# SCH_protopanda_v10.net
KiCad netlist of a schematic drawn in EasyEDA
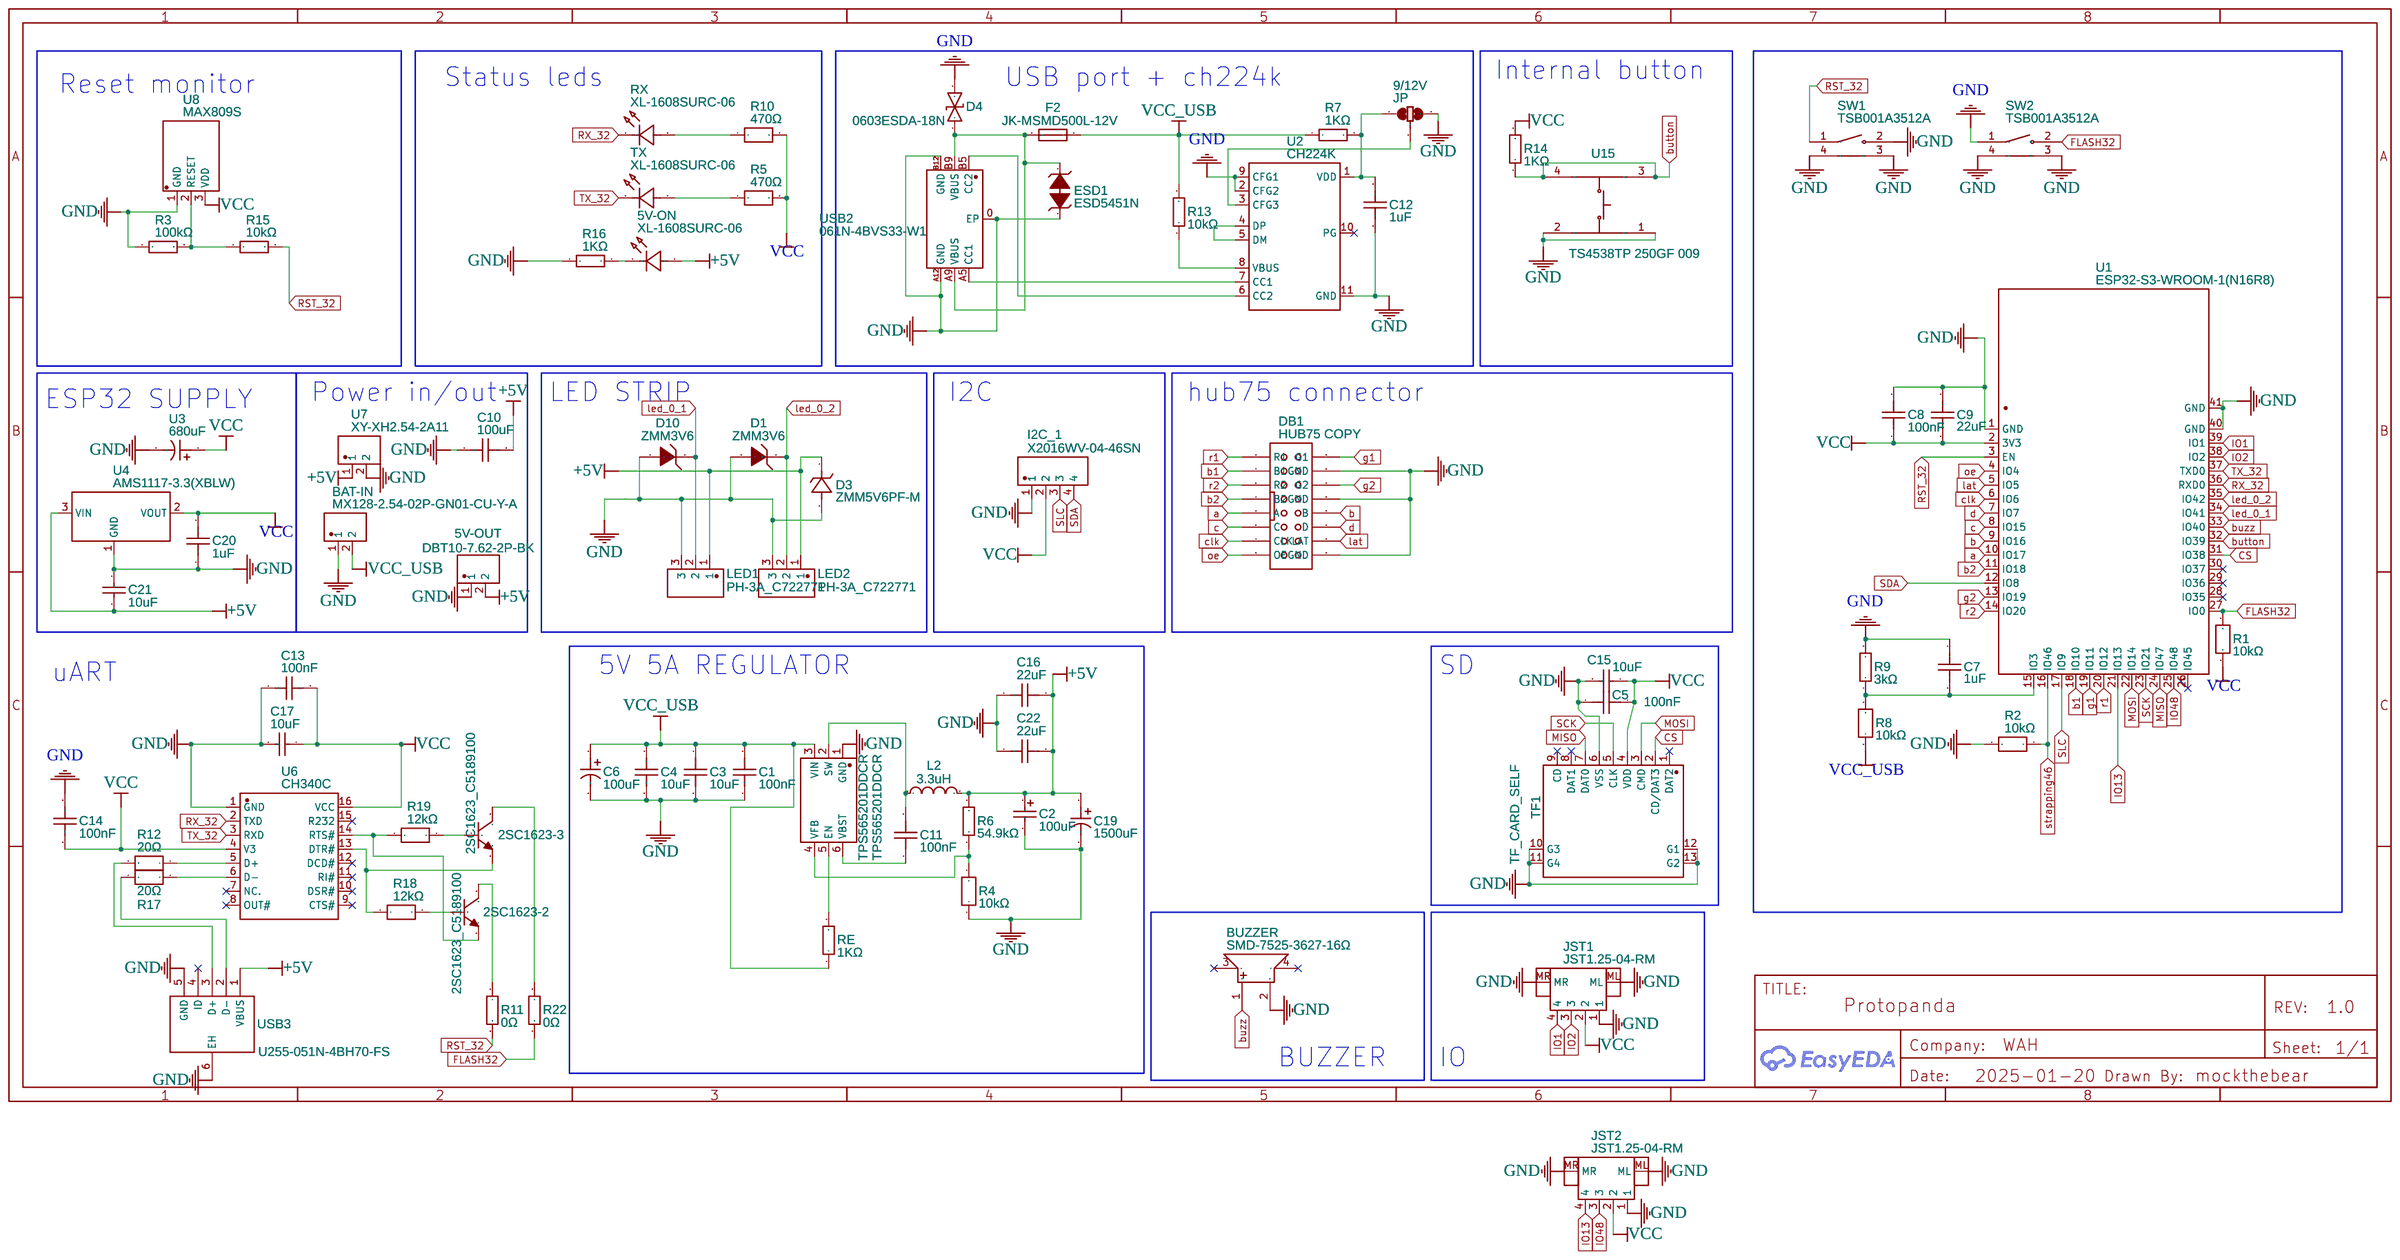
[diagram p0: schematic sheet]

(export (version "E")
  (design (tool "Eeschema 10.0.6"))
  (components
    (comp (ref "2SC1623-2")
      (value "2SC1623_C5189100")
      (fields (field (name "Manufacturer Part") "2SC1623") (field (name "Manufacturer") "HXY MOSFET(华轩阳电子)"))
      (libsource (lib "") (part "2SC1623_C5189100"))
    )
    (comp (ref "2SC1623-3")
      (value "2SC1623_C5189100")
      (fields (field (name "Manufacturer Part") "2SC1623") (field (name "Manufacturer") "HXY MOSFET(华轩阳电子)"))
      (libsource (lib "") (part "2SC1623_C5189100"))
    )
    (comp (ref "5V-ON")
      (value "XL-1608SURC-06")
      (fields (field (name "Manufacturer") "XINGLIGHT(成兴光)"))
      (libsource (lib "") (part "XL-1608SURC-06_1"))
    )
    (comp (ref "5V-OUT")
      (value "DBT10-7.62-2P-BK")
      (fields
        (field (name "Manufacturer Part") "DBT10-7.62-2P-BK-P")
        (field (name "Manufacturer") "DORABO(地博电气)")
      )
      (libsource (lib "") (part "DBT10-7.62-2P-BK"))
    )
    (comp (ref "9/12V") (value "JP") (libsource (lib "") (part "JUMPER-PAD-3-NOFULL_BOX_SILK")))
    (comp (ref "BAT-IN")
      (value "MX128-2.54-02P-GN01-CU-Y-A")
      (fields
        (field (name "Manufacturer Part") "MX128-2.54-02P-GN01-Cu-Y-A")
        (field (name "Manufacturer") "MAX(迈旭)")
      )
      (libsource (lib "") (part "MX128-2.54-02P-GN01-CU-Y-A"))
    )
    (comp (ref "BUZZER")
      (value "SMD-7525-3627-16Ω")
      (fields (field (name "Manufacturer") "S&S(海旭)"))
      (libsource (lib "") (part "SMD-7525-3627-16Ω"))
    )
    (comp (ref "C1")
      (value "100nF")
      (fields
        (field (name "Manufacturer Part") "CC0603KRX7R6BB104")
        (field (name "Manufacturer") "YAGEO(国巨)")
      )
      (libsource (lib "") (part "CC0603KRX7R6BB104_1"))
    )
    (comp (ref "C2")
      (value "100uF")
      (fields
        (field (name "Manufacturer Part") "T490A107M006ATE800")
        (field (name "Manufacturer") "KEMET(基美)")
      )
      (libsource (lib "") (part "T490A107M006ATE800"))
    )
    (comp (ref "C3")
      (value "10uF")
      (fields (field (name "Manufacturer Part") "CC0603CRNPO9BN5R1") (field (name "Manufacturer") "YAGEO"))
      (libsource (lib "") (part "CC0603CRNPO9BN5R1"))
    )
    (comp (ref "C4")
      (value "10uF")
      (fields (field (name "Manufacturer Part") "CC0603CRNPO9BN5R1") (field (name "Manufacturer") "YAGEO"))
      (libsource (lib "") (part "CC0603CRNPO9BN5R1"))
    )
    (comp (ref "C5")
      (value "100nF")
      (fields
        (field (name "Manufacturer Part") "CC0603KRX7R6BB104")
        (field (name "Manufacturer") "YAGEO(国巨)")
      )
      (libsource (lib "") (part "CC0603KRX7R6BB104"))
    )
    (comp (ref "C6")
      (value "100uF")
      (fields
        (field (name "Manufacturer Part") "RVT100UF25V67RV0011")
        (field (name "Manufacturer") "KNSCHA(科尼盛)")
      )
      (libsource (lib "") (part "RVT100UF25V67RV0011"))
    )
    (comp (ref "C7")
      (value "1uF")
      (fields
        (field (name "Manufacturer Part") "CS1608X7R105K250NRB")
        (field (name "Manufacturer") "Samwha Capacitor")
      )
      (libsource (lib "") (part "CS1608X7R105K250NRB_1"))
    )
    (comp (ref "C8")
      (value "100nF")
      (fields
        (field (name "Manufacturer Part") "CC0603KRX7R6BB104")
        (field (name "Manufacturer") "YAGEO(国巨)")
      )
      (libsource (lib "") (part "CC0603KRX7R6BB104_1"))
    )
    (comp (ref "C9")
      (value "22uF")
      (fields
        (field (name "Manufacturer Part") "GRM188R61A226ME15D")
        (field (name "Manufacturer") "muRata(村田)")
      )
      (libsource (lib "") (part "GRM188R61A226ME15D"))
    )
    (comp (ref "C10")
      (value "100uF")
      (fields
        (field (name "Manufacturer Part") "TCC1206X5R107M6R3HT")
        (field (name "Manufacturer") "CCTC(三环)")
      )
      (libsource (lib "") (part "TCC1206X5R107M6R3HT"))
    )
    (comp (ref "C11")
      (value "100nF")
      (fields
        (field (name "Manufacturer Part") "CC0603KRX7R6BB104")
        (field (name "Manufacturer") "YAGEO(国巨)")
      )
      (libsource (lib "") (part "CC0603KRX7R6BB104_1"))
    )
    (comp (ref "C12")
      (value "1uF")
      (fields (field (name "Manufacturer Part") "CC0603CRNPO9BN5R1") (field (name "Manufacturer") "YAGEO"))
      (libsource (lib "") (part "CC0603CRNPO9BN5R1"))
    )
    (comp (ref "C13")
      (value "100nF")
      (fields
        (field (name "Manufacturer Part") "CC0603KRX7R6BB104")
        (field (name "Manufacturer") "YAGEO(国巨)")
      )
      (libsource (lib "") (part "CC0603KRX7R6BB104"))
    )
    (comp (ref "C14")
      (value "100nF")
      (fields
        (field (name "Manufacturer Part") "CC0603KRX7R6BB104")
        (field (name "Manufacturer") "YAGEO(国巨)")
      )
      (libsource (lib "") (part "CC0603KRX7R6BB104_1"))
    )
    (comp (ref "C15")
      (value "10uF")
      (fields (field (name "Manufacturer Part") "CC0603MRX5R6BB106") (field (name "Manufacturer") "YAGEO"))
      (libsource (lib "") (part "CC0603MRX5R6BB106_1"))
    )
    (comp (ref "C16") (value "22uF") (libsource (lib "") (part "C_0805_US")))
    (comp (ref "C17")
      (value "10uF")
      (fields (field (name "Manufacturer Part") "CC0603KRX5R5BB106") (field (name "Manufacturer") "YAGEO"))
      (libsource (lib "") (part "CC0603KRX5R5BB106"))
    )
    (comp (ref "C19")
      (value "1500uF")
      (fields (field (name "Manufacturer Part") "189RV0022") (field (name "Manufacturer") "KNSCHA(科尼盛)"))
      (libsource (lib "") (part "189RV0022"))
    )
    (comp (ref "C20")
      (value "1uF")
      (fields
        (field (name "Manufacturer Part") "CS1608X7R105K250NRB")
        (field (name "Manufacturer") "Samwha Capacitor")
      )
      (libsource (lib "") (part "CS1608X7R105K250NRB"))
    )
    (comp (ref "C21")
      (value "10uF")
      (fields (field (name "Manufacturer Part") "CC0603MRX5R6BB106") (field (name "Manufacturer") "YAGEO"))
      (libsource (lib "") (part "CC0603MRX5R6BB106"))
    )
    (comp (ref "C22") (value "22uF") (libsource (lib "") (part "C_0805_US")))
    (comp (ref "D1")
      (value "ZMM3V6")
      (fields (field (name "Manufacturer Part") "ZMM3V6-M") (field (name "Manufacturer") "ST(先科)"))
      (libsource (lib "") (part "ZMM3V6"))
    )
    (comp (ref "D3")
      (value "ZMM5V6PF-M")
      (fields (field (name "Manufacturer") "ST(先科)"))
      (libsource (lib "") (part "ZMM5V6PF-M"))
    )
    (comp (ref "D4")
      (value "0603ESDA-18N")
      (fields (field (name "Manufacturer") "BORN(伯恩半导体)"))
      (libsource (lib "") (part "0603ESDA-18N"))
    )
    (comp (ref "D10")
      (value "ZMM3V6")
      (fields (field (name "Manufacturer Part") "ZMM3V6-M") (field (name "Manufacturer") "ST(先科)"))
      (libsource (lib "") (part "ZMM3V6"))
    )
    (comp (ref "DB1") (value "HUB75 COPY") (libsource (lib "") (part "HUB75 COPY")))
    (comp (ref "ESD1")
      (value "ESD5451N")
      (fields (field (name "Manufacturer") "UMW(广东友台半导体)"))
      (libsource (lib "") (part "ESD5451N"))
    )
    (comp (ref "F2")
      (value "JK-MSMD500L-12V")
      (fields (field (name "Manufacturer") "JK(金科)"))
      (libsource (lib "") (part "JK-MSMD500L-12V"))
    )
    (comp (ref "I2C_1")
      (value "X2016WV-04-46SN")
      (fields (field (name "Manufacturer") "XKB Connectivity(中国星坤)"))
      (libsource (lib "") (part "X2016WV-04-46SN"))
    )
    (comp (ref "JST1") (value "JST1.25-04-RM") (libsource (lib "") (part "JST1.25-04-RM")))
    (comp (ref "JST2") (value "JST1.25-04-RM") (libsource (lib "") (part "JST1.25-04-RM")))
    (comp (ref "L2")
      (value "3.3uH")
      (fields
        (field (name "Manufacturer Part") "PSPMAA1040H-3R3M-ANP")
        (field (name "Manufacturer") "PROD(谱罗德)")
      )
      (libsource (lib "") (part "PSPMAA1040H-3R3M-ANP"))
    )
    (comp (ref "LED1")
      (value "PH-3A_C722771")
      (fields (field (name "Manufacturer Part") "PH-3A") (field (name "Manufacturer") "CAX(创都)"))
      (libsource (lib "") (part "PH-3A_C722771"))
    )
    (comp (ref "LED2")
      (value "PH-3A_C722771")
      (fields (field (name "Manufacturer Part") "PH-3A") (field (name "Manufacturer") "CAX(创都)"))
      (libsource (lib "") (part "PH-3A_C722771"))
    )
    (comp (ref "R1")
      (value "10kΩ")
      (fields (field (name "Manufacturer Part") "FRC0603F4992TS") (field (name "Manufacturer") "FOJAN(富捷)"))
      (libsource (lib "") (part "FRC0603F4992TS"))
    )
    (comp (ref "R2")
      (value "10kΩ")
      (fields (field (name "Manufacturer Part") "FRC0603F4992TS") (field (name "Manufacturer") "FOJAN(富捷)"))
      (libsource (lib "") (part "FRC0603F4992TS_1"))
    )
    (comp (ref "R3")
      (value "100kΩ")
      (fields
        (field (name "Manufacturer Part") "CL0603JN100KP")
        (field (name "Manufacturer") "ResistorToday")
      )
      (libsource (lib "") (part "PTFR0603B10K0P9_1"))
    )
    (comp (ref "R4")
      (value "10kΩ")
      (fields (field (name "Manufacturer Part") "FRC0603F4992TS") (field (name "Manufacturer") "FOJAN(富捷)"))
      (libsource (lib "") (part "FRC0603F4992TS"))
    )
    (comp (ref "R5")
      (value "470Ω")
      (fields (field (name "Manufacturer Part") "CL0603JN470RP") (field (name "Manufacturer") "昶龙科技"))
      (libsource (lib "") (part "CL0603JN470RP"))
    )
    (comp (ref "R6")
      (value "54.9kΩ")
      (fields
        (field (name "Manufacturer Part") "RCT03365KFLF")
        (field (name "Manufacturer") "Hong Kong Resistors")
      )
      (libsource (lib "") (part "RCT03365KFLF"))
    )
    (comp (ref "R7")
      (value "1KΩ")
      (fields (field (name "Manufacturer Part") "HRC0603J102 ENTN") (field (name "Manufacturer") "HWA CHN"))
      (libsource (lib "") (part "CR0603FA56R0G"))
    )
    (comp (ref "R8")
      (value "10kΩ")
      (fields (field (name "Manufacturer Part") "FRC0603F4992TS") (field (name "Manufacturer") "FOJAN(富捷)"))
      (libsource (lib "") (part "FRC0603F4992TS"))
    )
    (comp (ref "R9")
      (value "3kΩ")
      (fields (field (name "Manufacturer Part") "RTT03302JTP") (field (name "Manufacturer") "RALEC(旺诠)"))
      (libsource (lib "") (part "RTT03302JTP"))
    )
    (comp (ref "R10")
      (value "470Ω")
      (fields (field (name "Manufacturer Part") "CL0603JN470RP") (field (name "Manufacturer") "昶龙科技"))
      (libsource (lib "") (part "CL0603JN470RP"))
    )
    (comp (ref "R11")
      (value "0Ω")
      (fields
        (field (name "Manufacturer Part") "AECR0603F100RK9")
        (field (name "Manufacturer") "ResistorToday")
      )
      (libsource (lib "") (part "AECR0603F100RK9_1"))
    )
    (comp (ref "R12")
      (value "20Ω")
      (fields (field (name "Manufacturer Part") "SCR0603F20R") (field (name "Manufacturer") "VO(翔胜)"))
      (libsource (lib "") (part "SCR0603F20R"))
    )
    (comp (ref "R13")
      (value "10kΩ")
      (fields
        (field (name "Manufacturer Part") "PTFR0603B10K0P9")
        (field (name "Manufacturer") "ResistorToday")
      )
      (libsource (lib "") (part "PTFR0603B10K0P9"))
    )
    (comp (ref "R14")
      (value "1KΩ")
      (fields (field (name "Manufacturer Part") "HRC0603J102 ENTN") (field (name "Manufacturer") "HWA CHN"))
      (libsource (lib "") (part "CR0603FA56R0G_1"))
    )
    (comp (ref "R15")
      (value "10kΩ")
      (fields
        (field (name "Manufacturer Part") "PTFR0603B10K0P9")
        (field (name "Manufacturer") "ResistorToday")
      )
      (libsource (lib "") (part "PTFR0603B10K0P9_1"))
    )
    (comp (ref "R16")
      (value "1KΩ")
      (fields (field (name "Manufacturer Part") "HRC0603J102 ENTN") (field (name "Manufacturer") "HWA CHN"))
      (libsource (lib "") (part "CR0603FA56R0G"))
    )
    (comp (ref "R17")
      (value "20Ω")
      (fields (field (name "Manufacturer Part") "SCR0603F20R") (field (name "Manufacturer") "VO(翔胜)"))
      (libsource (lib "") (part "SCR0603F20R_1"))
    )
    (comp (ref "R18")
      (value "12kΩ")
      (fields (field (name "Manufacturer Part") "FRC0603J123 TS") (field (name "Manufacturer") "FOJAN(富捷)"))
      (libsource (lib "") (part "FRC0603J123 TS"))
    )
    (comp (ref "R19")
      (value "12kΩ")
      (fields (field (name "Manufacturer Part") "FRC0603J123 TS") (field (name "Manufacturer") "FOJAN(富捷)"))
      (libsource (lib "") (part "FRC0603J123 TS"))
    )
    (comp (ref "R22")
      (value "0Ω")
      (fields
        (field (name "Manufacturer Part") "AECR0603F100RK9")
        (field (name "Manufacturer") "ResistorToday")
      )
      (libsource (lib "") (part "AECR0603F100RK9"))
    )
    (comp (ref "RE")
      (value "1KΩ")
      (fields (field (name "Manufacturer Part") "HRC0603J102 ENTN") (field (name "Manufacturer") "HWA CHN"))
      (libsource (lib "") (part "CR0603FA56R0G_2"))
    )
    (comp (ref "RX")
      (value "XL-1608SURC-06")
      (fields (field (name "Manufacturer") "XINGLIGHT(成兴光)"))
      (libsource (lib "") (part "XL-1608SURC-06_2"))
    )
    (comp (ref "SW1")
      (value "TSB001A3512A")
      (fields (field (name "Manufacturer") "BZCN(博众电气)"))
      (libsource (lib "") (part "TSB001A3512A"))
    )
    (comp (ref "SW2")
      (value "TSB001A3512A")
      (fields (field (name "Manufacturer") "BZCN(博众电气)"))
      (libsource (lib "") (part "TSB001A3512A"))
    )
    (comp (ref "TF1") (value "TF_CARD_SELF") (libsource (lib "") (part "TF_CARD_SELF")))
    (comp (ref "TPS565201DDCR")
      (value "TPS565201DDCR")
      (fields (field (name "Manufacturer") "TI(德州仪器)"))
      (libsource (lib "") (part "TPS565201DDCR"))
    )
    (comp (ref "TX")
      (value "XL-1608SURC-06")
      (fields (field (name "Manufacturer") "XINGLIGHT(成兴光)"))
      (libsource (lib "") (part "XL-1608SURC-06"))
    )
    (comp (ref "U1")
      (value "ESP32-S3-WROOM-1(N16R8)")
      (fields
        (field (name "Manufacturer Part") "ESP32-S3-WROOM-1-N16R8")
        (field (name "Manufacturer") "ESPRESSIF(乐鑫)")
      )
      (libsource (lib "") (part "ESP32-S3-WROOM-1(N16R8)"))
    )
    (comp (ref "U2")
      (value "CH224K")
      (fields (field (name "Manufacturer") "WCH(南京沁恒)"))
      (libsource (lib "") (part "CH224K"))
    )
    (comp (ref "U3")
      (value "680uF")
      (fields (field (name "Manufacturer Part") "189RV0015") (field (name "Manufacturer") "KNSCHA(科尼盛)"))
      (libsource (lib "") (part "189RV0015"))
    )
    (comp (ref "U4")
      (value "AMS1117-3.3(XBLW)")
      (fields (field (name "Manufacturer") "XBLW(芯伯乐)"))
      (libsource (lib "") (part "AMS1117-3.3(XBLW)"))
    )
    (comp (ref "U6")
      (value "CH340C")
      (fields (field (name "Manufacturer") "WCH(南京沁恒)"))
      (libsource (lib "") (part "CH340C"))
    )
    (comp (ref "U7")
      (value "XY-XH2.54-2A11")
      (fields (field (name "Manufacturer") "XYECONN(辛译)"))
      (libsource (lib "") (part "XY-XH2.54-2A11"))
    )
    (comp (ref "U8")
      (value "MAX809S")
      (fields (field (name "Manufacturer") "UMW(广东友台半导体)"))
      (libsource (lib "") (part "MAX809S"))
    )
    (comp (ref "U15")
      (value "TS4538TP 250GF 009")
      (fields
        (field (name "Manufacturer Part") "TS4538TP 250gf 009")
        (field (name "Manufacturer") "SHOU HAN(首韩)")
      )
      (libsource (lib "") (part "TS4538TP 250GF 009"))
    )
    (comp (ref "USB2")
      (value "061N-4BVS33-W1")
      (fields (field (name "Manufacturer") "HanElectricity(瀚源)"))
      (libsource (lib "") (part "061N-4BVS33-W1"))
    )
    (comp (ref "USB3")
      (value "U255-051N-4BH70-FS")
      (fields (field (name "Manufacturer") "XKB Connection(中国星坤)"))
      (libsource (lib "") (part "U255-051N-4BH70-FS"))
    )
  )
  (nets
    (net (code "1") (name "+5V") (class "Default")
      (node (ref "5V-ON") (pin "2") (pinfunction "A_2") (pintype "unspecified"))
      (node (ref "5V-OUT") (pin "2") (pinfunction "2_2") (pintype "unspecified"))
      (node (ref "C10") (pin "2") (pinfunction "2_2") (pintype "unspecified"))
      (node (ref "C16") (pin "2") (pinfunction "2_2") (pintype "unspecified"))
      (node (ref "C19") (pin "1") (pinfunction "1_1") (pintype "input"))
      (node (ref "C2") (pin "1") (pinfunction "1_1") (pintype "input"))
      (node (ref "C21") (pin "2") (pinfunction "2_2") (pintype "input"))
      (node (ref "C22") (pin "2") (pinfunction "2_2") (pintype "unspecified"))
      (node (ref "D3") (pin "1") (pinfunction "C_1") (pintype "unspecified"))
      (node (ref "L2") (pin "2") (pinfunction "2_2") (pintype "unspecified"))
      (node (ref "LED1") (pin "1") (pinfunction "1_1") (pintype "unspecified"))
      (node (ref "LED2") (pin "1") (pinfunction "1_1") (pintype "unspecified"))
      (node (ref "R6") (pin "2") (pinfunction "2_2") (pintype "unspecified"))
      (node (ref "U4") (pin "3") (pinfunction "VIN_3") (pintype "unspecified"))
      (node (ref "U7") (pin "1") (pinfunction "1_1") (pintype "unspecified"))
      (node (ref "USB3") (pin "1") (pinfunction "VBUS_1") (pintype "unspecified"))
    )
    (net (code "2") (name "CS") (class "Default")
      (node (ref "TF1") (pin "2") (pinfunction "CD/DAT3_2") (pintype "unspecified"))
      (node (ref "U1") (pin "31") (pinfunction "IO38_31") (pintype "unspecified"))
    )
    (net (code "3") (name "FLASH32") (class "Default")
      (node (ref "R1") (pin "2") (pinfunction "2_2") (pintype "unspecified"))
      (node (ref "R22") (pin "1") (pinfunction "1_1") (pintype "unspecified"))
      (node (ref "SW2") (pin "2") (pinfunction "2_2") (pintype "unspecified"))
      (node (ref "U1") (pin "27") (pinfunction "IO0_27") (pintype "unspecified"))
    )
    (net (code "4") (name "GND") (class "Default")
      (node (ref "5V-OUT") (pin "1") (pinfunction "1_1") (pintype "unspecified"))
      (node (ref "9/12V") (pin "3") (pinfunction "3_3") (pintype "unspecified"))
      (node (ref "BAT-IN") (pin "1") (pinfunction "1_1") (pintype "unspecified"))
      (node (ref "BUZZER") (pin "2") (pinfunction "2_2") (pintype "unspecified"))
      (node (ref "C1") (pin "1") (pinfunction "1_1") (pintype "unspecified"))
      (node (ref "C10") (pin "1") (pinfunction "1_1") (pintype "unspecified"))
      (node (ref "C12") (pin "2") (pinfunction "2_2") (pintype "unspecified"))
      (node (ref "C13") (pin "1") (pinfunction "1_1") (pintype "unspecified"))
      (node (ref "C14") (pin "2") (pinfunction "2_2") (pintype "unspecified"))
      (node (ref "C15") (pin "2") (pinfunction "2_2") (pintype "input"))
      (node (ref "C16") (pin "1") (pinfunction "1_1") (pintype "unspecified"))
      (node (ref "C17") (pin "2") (pinfunction "2_2") (pintype "input"))
      (node (ref "C19") (pin "2") (pinfunction "2_2") (pintype "input"))
      (node (ref "C2") (pin "2") (pinfunction "2_2") (pintype "input"))
      (node (ref "C20") (pin "1") (pinfunction "1_1") (pintype "unspecified"))
      (node (ref "C21") (pin "1") (pinfunction "1_1") (pintype "input"))
      (node (ref "C22") (pin "1") (pinfunction "1_1") (pintype "unspecified"))
      (node (ref "C3") (pin "2") (pinfunction "2_2") (pintype "unspecified"))
      (node (ref "C4") (pin "2") (pinfunction "2_2") (pintype "unspecified"))
      (node (ref "C5") (pin "1") (pinfunction "1_1") (pintype "unspecified"))
      (node (ref "C6") (pin "2") (pinfunction "2_2") (pintype "input"))
      (node (ref "C7") (pin "1") (pinfunction "1_1") (pintype "unspecified"))
      (node (ref "C8") (pin "2") (pinfunction "2_2") (pintype "unspecified"))
      (node (ref "C9") (pin "1") (pinfunction "1_1") (pintype "unspecified"))
      (node (ref "D1") (pin "2") (pinfunction "A_2") (pintype "unspecified"))
      (node (ref "D10") (pin "2") (pinfunction "A_2") (pintype "unspecified"))
      (node (ref "D3") (pin "2") (pinfunction "A_2") (pintype "unspecified"))
      (node (ref "D4") (pin "2") (pinfunction "2_2") (pintype "unspecified"))
      (node (ref "DB1") (pin "13") (pinfunction "GND_13") (pintype "unspecified"))
      (node (ref "DB1") (pin "15") (pinfunction "GND_15") (pintype "unspecified"))
      (node (ref "DB1") (pin "9") (pinfunction "GND_9") (pintype "unspecified"))
      (node (ref "ESD1") (pin "1") (pinfunction "1_1") (pintype "unspecified"))
      (node (ref "I2C_1") (pin "1") (pinfunction "1_1") (pintype "unspecified"))
      (node (ref "JST1") (pin "1") (pinfunction "1_1") (pintype "unspecified"))
      (node (ref "JST1") (pin "ML") (pinfunction "ML_ML") (pintype "unspecified"))
      (node (ref "JST1") (pin "MR") (pinfunction "MR_MR") (pintype "unspecified"))
      (node (ref "JST2") (pin "1") (pinfunction "1_1") (pintype "unspecified"))
      (node (ref "JST2") (pin "ML") (pinfunction "ML_ML") (pintype "unspecified"))
      (node (ref "JST2") (pin "MR") (pinfunction "MR_MR") (pintype "unspecified"))
      (node (ref "LED1") (pin "3") (pinfunction "3_3") (pintype "unspecified"))
      (node (ref "LED2") (pin "3") (pinfunction "3_3") (pintype "unspecified"))
      (node (ref "R16") (pin "1") (pinfunction "1_1") (pintype "input"))
      (node (ref "R2") (pin "2") (pinfunction "2_2") (pintype "unspecified"))
      (node (ref "R3") (pin "1") (pinfunction "1_1") (pintype "unspecified"))
      (node (ref "R4") (pin "1") (pinfunction "1_1") (pintype "unspecified"))
      (node (ref "R9") (pin "2") (pinfunction "2_2") (pintype "input"))
      (node (ref "SW1") (pin "2") (pinfunction "2_2") (pintype "unspecified"))
      (node (ref "SW1") (pin "3") (pinfunction "3_3") (pintype "unspecified"))
      (node (ref "SW1") (pin "4") (pinfunction "4_4") (pintype "unspecified"))
      (node (ref "SW2") (pin "1") (pinfunction "1_1") (pintype "unspecified"))
      (node (ref "SW2") (pin "3") (pinfunction "3_3") (pintype "unspecified"))
      (node (ref "SW2") (pin "4") (pinfunction "4_4") (pintype "unspecified"))
      (node (ref "TF1") (pin "10") (pinfunction "G3_10") (pintype "unspecified"))
      (node (ref "TF1") (pin "11") (pinfunction "G4_11") (pintype "unspecified"))
      (node (ref "TF1") (pin "12") (pinfunction "G1_12") (pintype "unspecified"))
      (node (ref "TF1") (pin "13") (pinfunction "G2_13") (pintype "unspecified"))
      (node (ref "TF1") (pin "6") (pinfunction "VSS_6") (pintype "unspecified"))
      (node (ref "TPS565201DDCR") (pin "1") (pinfunction "GND_1") (pintype "unspecified"))
      (node (ref "U1") (pin "1") (pinfunction "GND_1") (pintype "unspecified"))
      (node (ref "U1") (pin "40") (pinfunction "GND_40") (pintype "unspecified"))
      (node (ref "U1") (pin "41") (pinfunction "GND_41") (pintype "unspecified"))
      (node (ref "U15") (pin "1") (pinfunction "1_1") (pintype "unspecified"))
      (node (ref "U15") (pin "2") (pinfunction "2_2") (pintype "unspecified"))
      (node (ref "U2") (pin "11") (pinfunction "GND_11") (pintype "unspecified"))
      (node (ref "U2") (pin "2") (pinfunction "CFG2_2") (pintype "unspecified"))
      (node (ref "U2") (pin "9") (pinfunction "CFG1_9") (pintype "unspecified"))
      (node (ref "U3") (pin "2") (pinfunction "2_2") (pintype "input"))
      (node (ref "U4") (pin "1") (pinfunction "GND_1") (pintype "unspecified"))
      (node (ref "U6") (pin "1") (pinfunction "GND_1") (pintype "unspecified"))
      (node (ref "U7") (pin "2") (pinfunction "2_2") (pintype "unspecified"))
      (node (ref "U8") (pin "1") (pinfunction "GND_1") (pintype "unspecified"))
      (node (ref "USB2") (pin "0") (pinfunction "EP_0") (pintype "unspecified"))
      (node (ref "USB2") (pin "A12") (pinfunction "GND_A12") (pintype "unspecified"))
      (node (ref "USB2") (pin "B12") (pinfunction "GND_B12") (pintype "unspecified"))
      (node (ref "USB3") (pin "5") (pinfunction "GND_5") (pintype "unspecified"))
      (node (ref "USB3") (pin "6") (pinfunction "EH_6") (pintype "unspecified"))
    )
    (net (code "5") (name "IO1") (class "Default")
      (node (ref "JST1") (pin "4") (pinfunction "4_4") (pintype "unspecified"))
      (node (ref "U1") (pin "39") (pinfunction "IO1_39") (pintype "unspecified"))
    )
    (net (code "6") (name "IO2") (class "Default")
      (node (ref "JST1") (pin "3") (pinfunction "3_3") (pintype "unspecified"))
      (node (ref "U1") (pin "38") (pinfunction "IO2_38") (pintype "unspecified"))
    )
    (net (code "7") (name "IO13") (class "Default")
      (node (ref "JST2") (pin "4") (pinfunction "4_4") (pintype "unspecified"))
      (node (ref "U1") (pin "21") (pinfunction "IO13_21") (pintype "unspecified"))
    )
    (net (code "8") (name "IO48") (class "Default")
      (node (ref "JST2") (pin "3") (pinfunction "3_3") (pintype "unspecified"))
      (node (ref "U1") (pin "25") (pinfunction "IO48_25") (pintype "unspecified"))
    )
    (net (code "9") (name "MISO") (class "Default")
      (node (ref "TF1") (pin "7") (pinfunction "DAT0_7") (pintype "unspecified"))
      (node (ref "U1") (pin "24") (pinfunction "IO47_24") (pintype "unspecified"))
    )
    (net (code "10") (name "MOSI") (class "Default")
      (node (ref "TF1") (pin "3") (pinfunction "CMD_3") (pintype "unspecified"))
      (node (ref "U1") (pin "22") (pinfunction "IO14_22") (pintype "unspecified"))
    )
    (net (code "11") (name "Net-(2SC1623-2-B)") (class "Default")
      (node (ref "2SC1623-2") (pin "1") (pinfunction "B_1") (pintype "input"))
      (node (ref "R18") (pin "2") (pinfunction "2_2") (pintype "unspecified"))
    )
    (net (code "12") (name "Net-(2SC1623-2-C)") (class "Default")
      (node (ref "2SC1623-2") (pin "3") (pinfunction "C_3") (pintype "input"))
      (node (ref "R11") (pin "1") (pinfunction "1_1") (pintype "unspecified"))
    )
    (net (code "13") (name "Net-(2SC1623-2-E)") (class "Default")
      (node (ref "2SC1623-2") (pin "2") (pinfunction "E_2") (pintype "input"))
      (node (ref "R19") (pin "1") (pinfunction "1_1") (pintype "unspecified"))
      (node (ref "U6") (pin "14") (pinfunction "RTS#_14") (pintype "unspecified"))
    )
    (net (code "14") (name "Net-(2SC1623-3-B)") (class "Default")
      (node (ref "2SC1623-3") (pin "1") (pinfunction "B_1") (pintype "input"))
      (node (ref "R19") (pin "2") (pinfunction "2_2") (pintype "unspecified"))
    )
    (net (code "15") (name "Net-(2SC1623-3-C)") (class "Default")
      (node (ref "2SC1623-3") (pin "3") (pinfunction "C_3") (pintype "input"))
      (node (ref "R22") (pin "2") (pinfunction "2_2") (pintype "unspecified"))
    )
    (net (code "16") (name "Net-(2SC1623-3-E)") (class "Default")
      (node (ref "2SC1623-3") (pin "2") (pinfunction "E_2") (pintype "input"))
      (node (ref "R18") (pin "1") (pinfunction "1_1") (pintype "unspecified"))
      (node (ref "U6") (pin "13") (pinfunction "DTR#_13") (pintype "unspecified"))
    )
    (net (code "17") (name "Net-(5V-ON-K)") (class "Default")
      (node (ref "5V-ON") (pin "1") (pinfunction "K_1") (pintype "unspecified"))
      (node (ref "R16") (pin "2") (pinfunction "2_2") (pintype "input"))
    )
    (net (code "18") (name "Net-(D4-Pad1)") (class "Default")
      (node (ref "D4") (pin "1") (pinfunction "1_1") (pintype "unspecified"))
      (node (ref "ESD1") (pin "2") (pinfunction "2_2") (pintype "unspecified"))
      (node (ref "F2") (pin "2") (pinfunction "2_2") (pintype "unspecified"))
      (node (ref "USB2") (pin "A9") (pinfunction "VBUS_A9") (pintype "unspecified"))
      (node (ref "USB2") (pin "B9") (pinfunction "VBUS_B9") (pintype "unspecified"))
    )
    (net (code "19") (name "Net-(RX-A)") (class "Default")
      (node (ref "R10") (pin "1") (pinfunction "1_1") (pintype "unspecified"))
      (node (ref "RX") (pin "2") (pinfunction "A_2") (pintype "unspecified"))
    )
    (net (code "20") (name "Net-(TPS565201DDCR-EN)") (class "Default")
      (node (ref "RE") (pin "2") (pinfunction "2_2") (pintype "input"))
      (node (ref "TPS565201DDCR") (pin "5") (pinfunction "EN_5") (pintype "unspecified"))
    )
    (net (code "21") (name "Net-(TPS565201DDCR-SW)") (class "Default")
      (node (ref "C11") (pin "2") (pinfunction "2_2") (pintype "unspecified"))
      (node (ref "L2") (pin "1") (pinfunction "1_1") (pintype "unspecified"))
      (node (ref "TPS565201DDCR") (pin "2") (pinfunction "SW_2") (pintype "unspecified"))
    )
    (net (code "22") (name "Net-(TPS565201DDCR-VBST)") (class "Default")
      (node (ref "C11") (pin "1") (pinfunction "1_1") (pintype "unspecified"))
      (node (ref "TPS565201DDCR") (pin "6") (pinfunction "VBST_6") (pintype "unspecified"))
    )
    (net (code "23") (name "Net-(TPS565201DDCR-VFB)") (class "Default")
      (node (ref "R4") (pin "2") (pinfunction "2_2") (pintype "unspecified"))
      (node (ref "R6") (pin "1") (pinfunction "1_1") (pintype "unspecified"))
      (node (ref "TPS565201DDCR") (pin "4") (pinfunction "VFB_4") (pintype "unspecified"))
    )
    (net (code "24") (name "Net-(TX-A)") (class "Default")
      (node (ref "R5") (pin "1") (pinfunction "1_1") (pintype "unspecified"))
      (node (ref "TX") (pin "2") (pinfunction "A_2") (pintype "unspecified"))
    )
    (net (code "25") (name "Net-(U1-IO3)") (class "Default")
      (node (ref "C7") (pin "2") (pinfunction "2_2") (pintype "unspecified"))
      (node (ref "R8") (pin "2") (pinfunction "2_2") (pintype "unspecified"))
      (node (ref "R9") (pin "1") (pinfunction "1_1") (pintype "input"))
      (node (ref "U1") (pin "15") (pinfunction "IO3_15") (pintype "unspecified"))
    )
    (net (code "26") (name "Net-(U2-CC1)") (class "Default")
      (node (ref "U2") (pin "7") (pinfunction "CC1_7") (pintype "unspecified"))
      (node (ref "USB2") (pin "A5") (pinfunction "CC1_A5") (pintype "unspecified"))
    )
    (net (code "27") (name "Net-(U2-CC2)") (class "Default")
      (node (ref "U2") (pin "6") (pinfunction "CC2_6") (pintype "unspecified"))
      (node (ref "USB2") (pin "B5") (pinfunction "CC2_B5") (pintype "unspecified"))
    )
    (net (code "28") (name "Net-(U2-CFG3)") (class "Default")
      (node (ref "9/12V") (pin "2") (pinfunction "2_2") (pintype "unspecified"))
      (node (ref "U2") (pin "3") (pinfunction "CFG3_3") (pintype "unspecified"))
    )
    (net (code "29") (name "Net-(U2-DM)") (class "Default")
      (node (ref "U2") (pin "4") (pinfunction "DP_4") (pintype "unspecified"))
      (node (ref "U2") (pin "5") (pinfunction "DM_5") (pintype "unspecified"))
    )
    (net (code "30") (name "Net-(U2-VBUS)") (class "Default")
      (node (ref "R13") (pin "1") (pinfunction "1_1") (pintype "unspecified"))
      (node (ref "U2") (pin "8") (pinfunction "VBUS_8") (pintype "unspecified"))
    )
    (net (code "31") (name "Net-(U2-VDD)") (class "Default")
      (node (ref "9/12V") (pin "1") (pinfunction "1_1") (pintype "unspecified"))
      (node (ref "C12") (pin "1") (pinfunction "1_1") (pintype "unspecified"))
      (node (ref "R7") (pin "2") (pinfunction "2_2") (pintype "input"))
      (node (ref "U2") (pin "1") (pinfunction "VDD_1") (pintype "unspecified"))
    )
    (net (code "32") (name "Net-(U6-D+)") (class "Default")
      (node (ref "R12") (pin "1") (pinfunction "1_1") (pintype "unspecified"))
      (node (ref "U6") (pin "5") (pinfunction "D+_5") (pintype "unspecified"))
    )
    (net (code "33") (name "Net-(U6-D-)") (class "Default")
      (node (ref "R17") (pin "2") (pinfunction "2_2") (pintype "unspecified"))
      (node (ref "U6") (pin "6") (pinfunction "D-_6") (pintype "unspecified"))
    )
    (net (code "34") (name "Net-(U8-RESET)") (class "Default")
      (node (ref "R15") (pin "1") (pinfunction "1_1") (pintype "unspecified"))
      (node (ref "R3") (pin "2") (pinfunction "2_2") (pintype "unspecified"))
      (node (ref "U8") (pin "2") (pinfunction "RESET_2") (pintype "unspecified"))
    )
    (net (code "35") (name "Net-(USB3-D+)") (class "Default")
      (node (ref "R12") (pin "2") (pinfunction "2_2") (pintype "unspecified"))
      (node (ref "USB3") (pin "3") (pinfunction "D+_3") (pintype "unspecified"))
    )
    (net (code "36") (name "Net-(USB3-D-)") (class "Default")
      (node (ref "R17") (pin "1") (pinfunction "1_1") (pintype "unspecified"))
      (node (ref "USB3") (pin "2") (pinfunction "D-_2") (pintype "unspecified"))
    )
    (net (code "37") (name "RST_32") (class "Default")
      (node (ref "R11") (pin "2") (pinfunction "2_2") (pintype "unspecified"))
      (node (ref "R15") (pin "2") (pinfunction "2_2") (pintype "unspecified"))
      (node (ref "SW1") (pin "1") (pinfunction "1_1") (pintype "unspecified"))
      (node (ref "U1") (pin "3") (pinfunction "EN_3") (pintype "unspecified"))
    )
    (net (code "38") (name "RX_32") (class "Default")
      (node (ref "RX") (pin "1") (pinfunction "K_1") (pintype "unspecified"))
      (node (ref "U1") (pin "36") (pinfunction "RXD0_36") (pintype "unspecified"))
      (node (ref "U6") (pin "2") (pinfunction "TXD_2") (pintype "unspecified"))
    )
    (net (code "39") (name "SCK") (class "Default")
      (node (ref "TF1") (pin "5") (pinfunction "CLK_5") (pintype "unspecified"))
      (node (ref "U1") (pin "23") (pinfunction "IO21_23") (pintype "unspecified"))
    )
    (net (code "40") (name "SDA") (class "Default")
      (node (ref "I2C_1") (pin "4") (pinfunction "4_4") (pintype "unspecified"))
      (node (ref "U1") (pin "12") (pinfunction "IO8_12") (pintype "unspecified"))
    )
    (net (code "41") (name "SLC") (class "Default")
      (node (ref "I2C_1") (pin "3") (pinfunction "3_3") (pintype "unspecified"))
      (node (ref "U1") (pin "17") (pinfunction "IO9_17") (pintype "unspecified"))
    )
    (net (code "42") (name "TX_32") (class "Default")
      (node (ref "TX") (pin "1") (pinfunction "K_1") (pintype "unspecified"))
      (node (ref "U1") (pin "37") (pinfunction "TXD0_37") (pintype "unspecified"))
      (node (ref "U6") (pin "3") (pinfunction "RXD_3") (pintype "unspecified"))
    )
    (net (code "43") (name "VCC") (class "Default")
      (node (ref "C13") (pin "2") (pinfunction "2_2") (pintype "unspecified"))
      (node (ref "C14") (pin "1") (pinfunction "1_1") (pintype "unspecified"))
      (node (ref "C15") (pin "1") (pinfunction "1_1") (pintype "input"))
      (node (ref "C17") (pin "1") (pinfunction "1_1") (pintype "input"))
      (node (ref "C20") (pin "2") (pinfunction "2_2") (pintype "unspecified"))
      (node (ref "C5") (pin "2") (pinfunction "2_2") (pintype "unspecified"))
      (node (ref "C8") (pin "1") (pinfunction "1_1") (pintype "unspecified"))
      (node (ref "C9") (pin "2") (pinfunction "2_2") (pintype "unspecified"))
      (node (ref "I2C_1") (pin "2") (pinfunction "2_2") (pintype "unspecified"))
      (node (ref "JST1") (pin "2") (pinfunction "2_2") (pintype "unspecified"))
      (node (ref "JST2") (pin "2") (pinfunction "2_2") (pintype "unspecified"))
      (node (ref "R1") (pin "1") (pinfunction "1_1") (pintype "unspecified"))
      (node (ref "R10") (pin "2") (pinfunction "2_2") (pintype "unspecified"))
      (node (ref "R14") (pin "2") (pinfunction "2_2") (pintype "input"))
      (node (ref "R5") (pin "2") (pinfunction "2_2") (pintype "unspecified"))
      (node (ref "TF1") (pin "4") (pinfunction "VDD_4") (pintype "unspecified"))
      (node (ref "U1") (pin "2") (pinfunction "3V3_2") (pintype "unspecified"))
      (node (ref "U3") (pin "1") (pinfunction "1_1") (pintype "input"))
      (node (ref "U4") (pin "2") (pinfunction "VOUT_2") (pintype "unspecified"))
      (node (ref "U6") (pin "16") (pinfunction "VCC_16") (pintype "unspecified"))
      (node (ref "U6") (pin "4") (pinfunction "V3_4") (pintype "unspecified"))
      (node (ref "U8") (pin "3") (pinfunction "VDD_3") (pintype "unspecified"))
    )
    (net (code "44") (name "VCC_USB") (class "Default")
      (node (ref "BAT-IN") (pin "2") (pinfunction "2_2") (pintype "unspecified"))
      (node (ref "C1") (pin "2") (pinfunction "2_2") (pintype "unspecified"))
      (node (ref "C3") (pin "1") (pinfunction "1_1") (pintype "unspecified"))
      (node (ref "C4") (pin "1") (pinfunction "1_1") (pintype "unspecified"))
      (node (ref "C6") (pin "1") (pinfunction "1_1") (pintype "input"))
      (node (ref "F2") (pin "1") (pinfunction "1_1") (pintype "unspecified"))
      (node (ref "R13") (pin "2") (pinfunction "2_2") (pintype "unspecified"))
      (node (ref "R7") (pin "1") (pinfunction "1_1") (pintype "input"))
      (node (ref "R8") (pin "1") (pinfunction "1_1") (pintype "unspecified"))
      (node (ref "RE") (pin "1") (pinfunction "1_1") (pintype "input"))
      (node (ref "TPS565201DDCR") (pin "3") (pinfunction "VIN_3") (pintype "unspecified"))
    )
    (net (code "45") (name "a") (class "Default")
      (node (ref "DB1") (pin "5") (pinfunction "A_5") (pintype "unspecified"))
      (node (ref "U1") (pin "10") (pinfunction "IO17_10") (pintype "unspecified"))
    )
    (net (code "46") (name "b") (class "Default")
      (node (ref "DB1") (pin "12") (pinfunction "B_12") (pintype "unspecified"))
      (node (ref "U1") (pin "9") (pinfunction "IO16_9") (pintype "unspecified"))
    )
    (net (code "47") (name "b1") (class "Default")
      (node (ref "DB1") (pin "2") (pinfunction "B1_2") (pintype "unspecified"))
      (node (ref "U1") (pin "18") (pinfunction "IO10_18") (pintype "unspecified"))
    )
    (net (code "48") (name "b2") (class "Default")
      (node (ref "DB1") (pin "4") (pinfunction "B2_4") (pintype "unspecified"))
      (node (ref "U1") (pin "11") (pinfunction "IO18_11") (pintype "unspecified"))
    )
    (net (code "49") (name "button") (class "Default")
      (node (ref "R14") (pin "1") (pinfunction "1_1") (pintype "input"))
      (node (ref "U1") (pin "32") (pinfunction "IO39_32") (pintype "unspecified"))
      (node (ref "U15") (pin "3") (pinfunction "3_3") (pintype "unspecified"))
      (node (ref "U15") (pin "4") (pinfunction "4_4") (pintype "unspecified"))
    )
    (net (code "50") (name "buzz") (class "Default")
      (node (ref "BUZZER") (pin "1") (pinfunction "1_1") (pintype "unspecified"))
      (node (ref "U1") (pin "33") (pinfunction "IO40_33") (pintype "unspecified"))
    )
    (net (code "51") (name "c") (class "Default")
      (node (ref "DB1") (pin "6") (pinfunction "C_6") (pintype "unspecified"))
      (node (ref "U1") (pin "8") (pinfunction "IO15_8") (pintype "unspecified"))
    )
    (net (code "52") (name "clk") (class "Default")
      (node (ref "DB1") (pin "7") (pinfunction "CLK_7") (pintype "unspecified"))
      (node (ref "U1") (pin "6") (pinfunction "IO6_6") (pintype "unspecified"))
    )
    (net (code "53") (name "d") (class "Default")
      (node (ref "DB1") (pin "11") (pinfunction "D_11") (pintype "unspecified"))
      (node (ref "U1") (pin "7") (pinfunction "IO7_7") (pintype "unspecified"))
    )
    (net (code "54") (name "g1") (class "Default")
      (node (ref "DB1") (pin "16") (pinfunction "G1_16") (pintype "unspecified"))
      (node (ref "U1") (pin "19") (pinfunction "IO11_19") (pintype "unspecified"))
    )
    (net (code "55") (name "g2") (class "Default")
      (node (ref "DB1") (pin "14") (pinfunction "G2_14") (pintype "unspecified"))
      (node (ref "U1") (pin "13") (pinfunction "IO19_13") (pintype "unspecified"))
    )
    (net (code "56") (name "lat") (class "Default")
      (node (ref "DB1") (pin "10") (pinfunction "LAT_10") (pintype "unspecified"))
      (node (ref "U1") (pin "5") (pinfunction "IO5_5") (pintype "unspecified"))
    )
    (net (code "57") (name "led_0_1") (class "Default")
      (node (ref "D10") (pin "1") (pinfunction "C_1") (pintype "unspecified"))
      (node (ref "LED1") (pin "2") (pinfunction "2_2") (pintype "unspecified"))
      (node (ref "U1") (pin "34") (pinfunction "IO41_34") (pintype "unspecified"))
    )
    (net (code "58") (name "led_0_2") (class "Default")
      (node (ref "D1") (pin "1") (pinfunction "C_1") (pintype "unspecified"))
      (node (ref "LED2") (pin "2") (pinfunction "2_2") (pintype "unspecified"))
      (node (ref "U1") (pin "35") (pinfunction "IO42_35") (pintype "unspecified"))
    )
    (net (code "59") (name "oe") (class "Default")
      (node (ref "DB1") (pin "8") (pinfunction "OE_8") (pintype "unspecified"))
      (node (ref "U1") (pin "4") (pinfunction "IO4_4") (pintype "unspecified"))
    )
    (net (code "60") (name "r1") (class "Default")
      (node (ref "DB1") (pin "1") (pinfunction "R1_1") (pintype "unspecified"))
      (node (ref "U1") (pin "20") (pinfunction "IO12_20") (pintype "unspecified"))
    )
    (net (code "61") (name "r2") (class "Default")
      (node (ref "DB1") (pin "3") (pinfunction "R2_3") (pintype "unspecified"))
      (node (ref "U1") (pin "14") (pinfunction "IO20_14") (pintype "unspecified"))
    )
    (net (code "62") (name "strapping46") (class "Default")
      (node (ref "R2") (pin "1") (pinfunction "1_1") (pintype "unspecified"))
      (node (ref "U1") (pin "16") (pinfunction "IO46_16") (pintype "unspecified"))
    )
    (net (code "63") (name "unconnected-(BUZZER-Pad3)") (class "Default")
      (node (ref "BUZZER") (pin "3") (pinfunction "3_3") (pintype "unspecified+no_connect"))
    )
    (net (code "64") (name "unconnected-(BUZZER-Pad4)") (class "Default")
      (node (ref "BUZZER") (pin "4") (pinfunction "4_4") (pintype "unspecified+no_connect"))
    )
    (net (code "65") (name "unconnected-(TF1-CD-Pad9)") (class "Default")
      (node (ref "TF1") (pin "9") (pinfunction "CD_9") (pintype "unspecified+no_connect"))
    )
    (net (code "66") (name "unconnected-(TF1-DAT1-Pad8)") (class "Default")
      (node (ref "TF1") (pin "8") (pinfunction "DAT1_8") (pintype "unspecified+no_connect"))
    )
    (net (code "67") (name "unconnected-(TF1-DAT2-Pad1)") (class "Default")
      (node (ref "TF1") (pin "1") (pinfunction "DAT2_1") (pintype "unspecified+no_connect"))
    )
    (net (code "68") (name "unconnected-(U1-IO35-Pad28)") (class "Default")
      (node (ref "U1") (pin "28") (pinfunction "IO35_28") (pintype "unspecified+no_connect"))
    )
    (net (code "69") (name "unconnected-(U1-IO36-Pad29)") (class "Default")
      (node (ref "U1") (pin "29") (pinfunction "IO36_29") (pintype "unspecified+no_connect"))
    )
    (net (code "70") (name "unconnected-(U1-IO37-Pad30)") (class "Default")
      (node (ref "U1") (pin "30") (pinfunction "IO37_30") (pintype "unspecified+no_connect"))
    )
    (net (code "71") (name "unconnected-(U1-IO45-Pad26)") (class "Default")
      (node (ref "U1") (pin "26") (pinfunction "IO45_26") (pintype "unspecified+no_connect"))
    )
    (net (code "72") (name "unconnected-(U2-PG-Pad10)") (class "Default")
      (node (ref "U2") (pin "10") (pinfunction "PG_10") (pintype "unspecified+no_connect"))
    )
    (net (code "73") (name "unconnected-(U6-CTS#-Pad9)") (class "Default")
      (node (ref "U6") (pin "9") (pinfunction "CTS#_9") (pintype "unspecified+no_connect"))
    )
    (net (code "74") (name "unconnected-(U6-DCD#-Pad12)") (class "Default")
      (node (ref "U6") (pin "12") (pinfunction "DCD#_12") (pintype "unspecified+no_connect"))
    )
    (net (code "75") (name "unconnected-(U6-DSR#-Pad10)") (class "Default")
      (node (ref "U6") (pin "10") (pinfunction "DSR#_10") (pintype "unspecified+no_connect"))
    )
    (net (code "76") (name "unconnected-(U6-NC.-Pad7)") (class "Default")
      (node (ref "U6") (pin "7") (pinfunction "NC._7") (pintype "unspecified+no_connect"))
    )
    (net (code "77") (name "unconnected-(U6-OUT#-Pad8)") (class "Default")
      (node (ref "U6") (pin "8") (pinfunction "OUT#_8") (pintype "unspecified+no_connect"))
    )
    (net (code "78") (name "unconnected-(U6-R232-Pad15)") (class "Default")
      (node (ref "U6") (pin "15") (pinfunction "R232_15") (pintype "unspecified+no_connect"))
    )
    (net (code "79") (name "unconnected-(U6-RI#-Pad11)") (class "Default")
      (node (ref "U6") (pin "11") (pinfunction "RI#_11") (pintype "unspecified+no_connect"))
    )
    (net (code "80") (name "unconnected-(USB3-ID-Pad4)") (class "Default")
      (node (ref "USB3") (pin "4") (pinfunction "ID_4") (pintype "unspecified+no_connect"))
    )
  )
)
